# RSX11_SDCard.net
KiCad netlist of a schematic drawn in Altium Designer
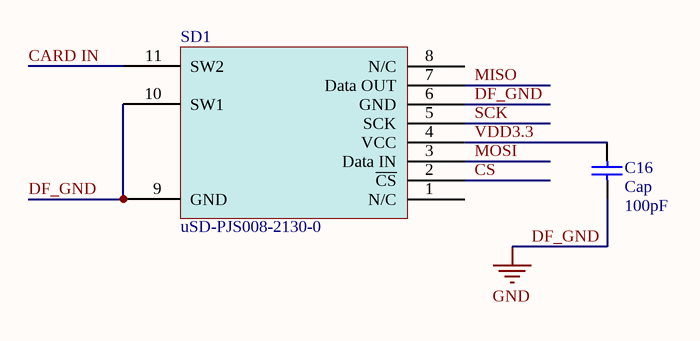
[diagram p0: RSX11_SDCard.SchDoc]

(export (version "E")
  (design (tool "Eeschema 10.0.6"))
  (components
    (comp (ref "C16")
      (value "Cap")
      (footprint "C1206")
      (description "Capacitor")
      (fields (field (name "ALTIUM_VALUE") "100pF") (field (name "PUBLISHER") "Altium Limited"))
      (libsource (lib "Miscellaneous Devices") (part "Cap"))
    )
    (comp (ref "SD1")
      (value "uSD-PJS008-2130-0")
      (footprint "microSD_push-push")
      (description "RockOn 2016 SD card midification (part number PJS008-2130-0) -Jesse Austin")
      (libsource (lib "USD CARD") (part "microSD_card_push-push"))
    )
  )
  (nets
    (net (code "1") (name "/CARD IN") (class "Default")
      (node (ref "SD1") (pin "11") (pinfunction "SW2_11") (pintype "passive"))
    )
    (net (code "2") (name "/CS") (class "Default")
      (node (ref "SD1") (pin "2") (pinfunction "~{CS}_2") (pintype "passive"))
    )
    (net (code "3") (name "/MISO") (class "Default")
      (node (ref "SD1") (pin "7") (pinfunction "Data_OUT_7") (pintype "passive"))
    )
    (net (code "4") (name "/MOSI") (class "Default")
      (node (ref "SD1") (pin "3") (pinfunction "Data_IN_3") (pintype "passive"))
    )
    (net (code "5") (name "/SCK") (class "Default")
      (node (ref "SD1") (pin "5") (pinfunction "SCK_5") (pintype "passive"))
    )
    (net (code "6") (name "/VDD3.3") (class "Default")
      (node (ref "C16") (pin "1") (pinfunction "1_1") (pintype "passive"))
      (node (ref "SD1") (pin "4") (pinfunction "VCC_4") (pintype "passive"))
    )
    (net (code "7") (name "GND") (class "Default")
      (node (ref "C16") (pin "2") (pinfunction "2_2") (pintype "passive"))
      (node (ref "SD1") (pin "10") (pinfunction "SW1_10") (pintype "passive"))
      (node (ref "SD1") (pin "6") (pinfunction "GND_6") (pintype "passive"))
      (node (ref "SD1") (pin "9") (pinfunction "GND_9") (pintype "passive"))
    )
    (net (code "8") (name "unconnected-(SD1-N{slash}C-Pad1)") (class "Default")
      (node (ref "SD1") (pin "1") (pinfunction "N/C_1") (pintype "passive"))
    )
    (net (code "9") (name "unconnected-(SD1-N{slash}C-Pad8)") (class "Default")
      (node (ref "SD1") (pin "8") (pinfunction "N/C_8") (pintype "passive"))
    )
  )
)
